# logic.net
KiCad netlist of a schematic drawn in EAGLE
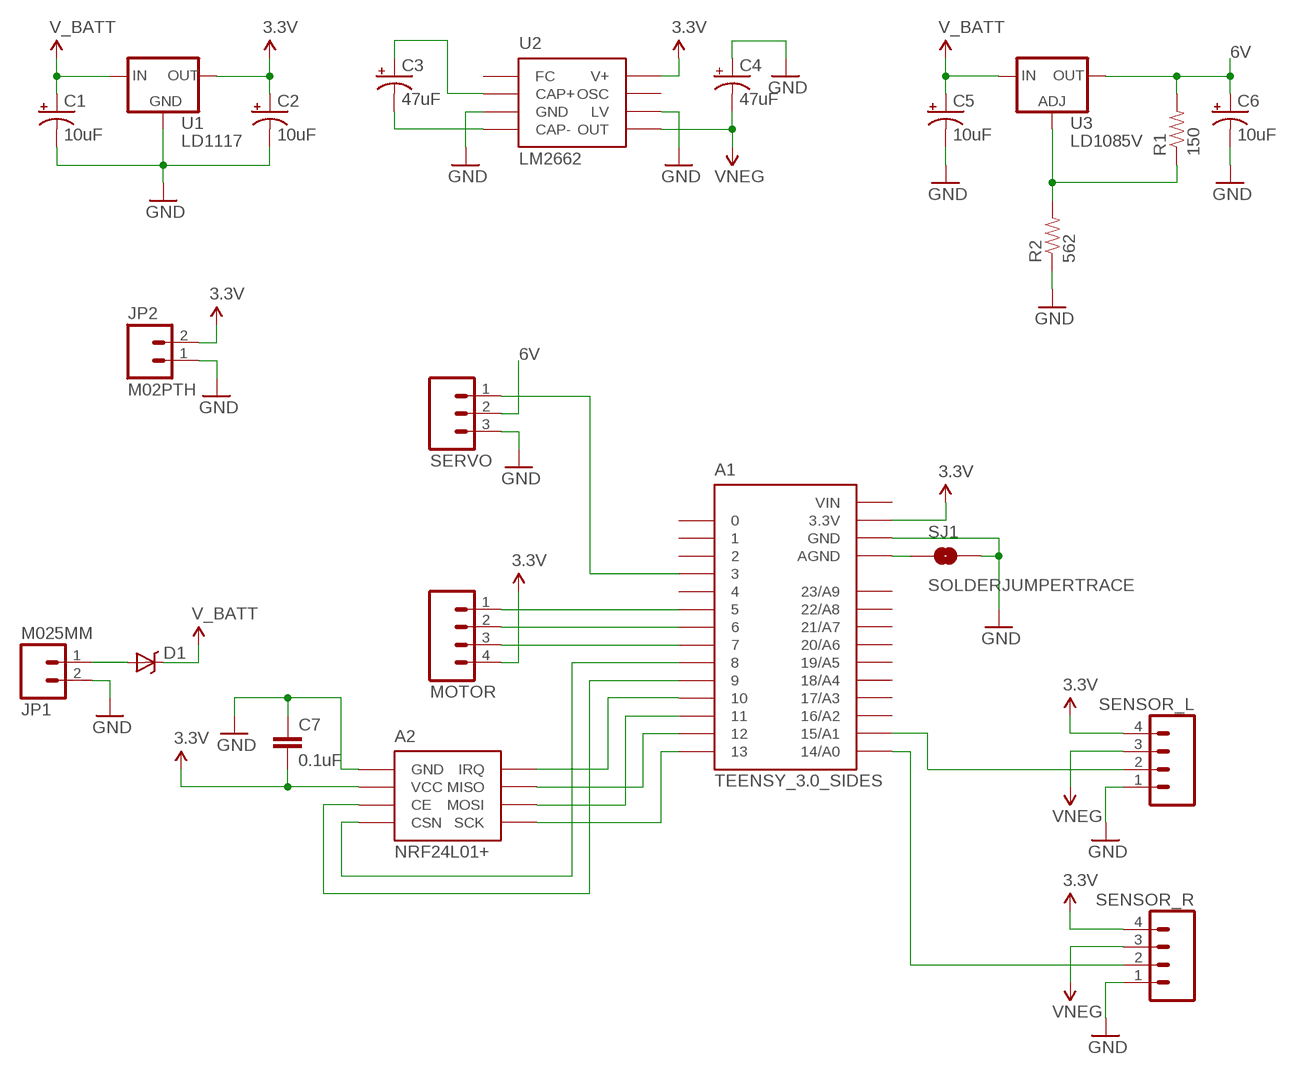
[diagram p0: schematic, sheet 1]

(export (version "E")
  (design (tool "Eeschema 10.0.6"))
  (components
    (comp (ref "A1")
      (value "TEENSY_3.0_SIDES")
      (footprint "eagle-import:TEENSY_3.0_SIDES")
      (libsource (lib "eagle-import") (part "TEENSY_3.0_SIDES"))
    )
    (comp (ref "A2")
      (value "NRF24L01+")
      (footprint "eagle-import:NRF24L01+")
      (libsource (lib "eagle-import") (part "NRF24L01+"))
    )
    (comp (ref "C1")
      (value "10uF")
      (footprint "eagle-import:E2-4")
      (libsource (lib "eagle-import") (part "CPOL-USE2-4"))
    )
    (comp (ref "C2")
      (value "10uF")
      (footprint "eagle-import:E2-4")
      (libsource (lib "eagle-import") (part "CPOL-USE2-4"))
    )
    (comp (ref "C3")
      (value "47uF")
      (footprint "eagle-import:CPOL-RADIAL-100UF-25V")
      (libsource (lib "eagle-import") (part "CAP_POLPTH1"))
    )
    (comp (ref "C4")
      (value "47uF")
      (footprint "eagle-import:CPOL-RADIAL-100UF-25V")
      (libsource (lib "eagle-import") (part "CAP_POLPTH1"))
    )
    (comp (ref "C5")
      (value "10uF")
      (footprint "eagle-import:E2-4")
      (libsource (lib "eagle-import") (part "CPOL-USE2-4"))
    )
    (comp (ref "C6")
      (value "10uF")
      (footprint "eagle-import:E2-4")
      (libsource (lib "eagle-import") (part "CPOL-USE2-4"))
    )
    (comp (ref "C7")
      (value "0.1uF")
      (footprint "eagle-import:0805")
      (libsource (lib "eagle-import") (part "CAP0805"))
    )
    (comp (ref "D1")
      (value "DIODE-SCHOTTKY_")
      (footprint "eagle-import:SMA-DIODE")
      (libsource (lib "eagle-import") (part "DIODE-SCHOTTKY_"))
    )
    (comp (ref "JP1")
      (value "M025MM")
      (footprint "eagle-import:SCREWTERMINAL-5MM-2")
      (libsource (lib "eagle-import") (part "M025MM"))
    )
    (comp (ref "JP2")
      (value "M02PTH")
      (footprint "eagle-import:1X02")
      (libsource (lib "eagle-import") (part "M02PTH"))
    )
    (comp (ref "MOTOR")
      (value "M04POLAR_LOCK")
      (footprint "eagle-import:MOLEX-1X4_LOCK")
      (libsource (lib "eagle-import") (part "M04POLAR_LOCK"))
    )
    (comp (ref "R1")
      (value "150")
      (footprint "eagle-import:0805")
      (libsource (lib "eagle-import") (part "RESISTOR0805-RES"))
    )
    (comp (ref "R2")
      (value "562")
      (footprint "eagle-import:0805")
      (libsource (lib "eagle-import") (part "RESISTOR0805-RES"))
    )
    (comp (ref "SENSOR_L")
      (value "M04POLAR_LOCK")
      (footprint "eagle-import:MOLEX-1X4_LOCK")
      (libsource (lib "eagle-import") (part "M04POLAR_LOCK"))
    )
    (comp (ref "SENSOR_R")
      (value "M04POLAR_LOCK")
      (footprint "eagle-import:MOLEX-1X4_LOCK")
      (libsource (lib "eagle-import") (part "M04POLAR_LOCK"))
    )
    (comp (ref "SERVO")
      (value "M03LOCK_LONGPADS")
      (footprint "eagle-import:1X03_LOCK_LONGPADS")
      (libsource (lib "eagle-import") (part "M03LOCK_LONGPADS"))
    )
    (comp (ref "SJ1")
      (value "SOLDERJUMPERTRACE")
      (footprint "eagle-import:SJ_2S-TRACE")
      (libsource (lib "eagle-import") (part "SOLDERJUMPERTRACE"))
    )
    (comp (ref "U1")
      (value "LD1117")
      (footprint "eagle-import:SOT-223")
      (libsource (lib "eagle-import") (part "LD1117"))
    )
    (comp (ref "U2")
      (value "LM2662")
      (footprint "eagle-import:SOIC-8")
      (libsource (lib "eagle-import") (part "LM2662"))
    )
    (comp (ref "U3")
      (value "LD1085V")
      (footprint "eagle-import:317TS")
      (libsource (lib "eagle-import") (part "LM317TS"))
    )
  )
  (nets
    (net (code "1") (name "/6V") (class "Default")
      (node (ref "C6") (pin "+") (pinfunction "+_+") (pintype "passive"))
      (node (ref "R1") (pin "2") (pinfunction "2_2") (pintype "passive"))
      (node (ref "SERVO") (pin "2") (pinfunction "2_2") (pintype "passive"))
      (node (ref "U3") (pin "2") (pinfunction "OUT_2") (pintype "passive"))
    )
    (net (code "2") (name "/VIN") (class "Default")
      (node (ref "A1") (pin "VIN") (pinfunction "VIN_VIN") (pintype "power_in"))
    )
    (net (code "3") (name "3.3V") (class "Default")
      (node (ref "A1") (pin "3.3V") (pinfunction "3.3V_3.3V") (pintype "power_in"))
      (node (ref "A2") (pin "2") (pinfunction "VCC_2") (pintype "bidirectional"))
      (node (ref "C2") (pin "+") (pinfunction "+_+") (pintype "passive"))
      (node (ref "C7") (pin "2") (pinfunction "2_2") (pintype "passive"))
      (node (ref "JP2") (pin "2") (pinfunction "2_2") (pintype "passive"))
      (node (ref "MOTOR") (pin "4") (pinfunction "4_4") (pintype "passive"))
      (node (ref "SENSOR_L") (pin "4") (pinfunction "4_4") (pintype "passive"))
      (node (ref "SENSOR_R") (pin "4") (pinfunction "4_4") (pintype "passive"))
      (node (ref "U1") (pin "2") (pinfunction "OUT_2") (pintype "passive"))
      (node (ref "U1") (pin "4") (pinfunction "OUT_4") (pintype "passive"))
      (node (ref "U2") (pin "8") (pinfunction "V+_8") (pintype "bidirectional"))
    )
    (net (code "4") (name "GND") (class "Default")
      (node (ref "A1") (pin "GND") (pinfunction "GND_GND") (pintype "power_in"))
      (node (ref "A2") (pin "1") (pinfunction "GND_1") (pintype "bidirectional"))
      (node (ref "C1") (pin "-") (pinfunction "-_-") (pintype "passive"))
      (node (ref "C2") (pin "-") (pinfunction "-_-") (pintype "passive"))
      (node (ref "C4") (pin "1") (pinfunction "+_1") (pintype "passive"))
      (node (ref "C5") (pin "-") (pinfunction "-_-") (pintype "passive"))
      (node (ref "C6") (pin "-") (pinfunction "-_-") (pintype "passive"))
      (node (ref "C7") (pin "1") (pinfunction "1_1") (pintype "passive"))
      (node (ref "JP1") (pin "2") (pinfunction "2_2") (pintype "passive"))
      (node (ref "JP2") (pin "1") (pinfunction "1_1") (pintype "passive"))
      (node (ref "R2") (pin "1") (pinfunction "1_1") (pintype "passive"))
      (node (ref "SENSOR_L") (pin "1") (pinfunction "1_1") (pintype "passive"))
      (node (ref "SENSOR_R") (pin "1") (pinfunction "1_1") (pintype "passive"))
      (node (ref "SERVO") (pin "3") (pinfunction "3_3") (pintype "passive"))
      (node (ref "SJ1") (pin "2") (pinfunction "2_2") (pintype "passive"))
      (node (ref "U1") (pin "1") (pinfunction "GND_1") (pintype "input"))
      (node (ref "U2") (pin "3") (pinfunction "GND_3") (pintype "bidirectional"))
      (node (ref "U2") (pin "6") (pinfunction "LV_6") (pintype "bidirectional"))
    )
    (net (code "5") (name "Net-(A1-Pad3)") (class "Default")
      (node (ref "A1") (pin "3") (pinfunction "3_3") (pintype "bidirectional"))
      (node (ref "SERVO") (pin "1") (pinfunction "1_1") (pintype "passive"))
    )
    (net (code "6") (name "Net-(A1-Pad5)") (class "Default")
      (node (ref "A1") (pin "5") (pinfunction "5_5") (pintype "bidirectional"))
      (node (ref "MOTOR") (pin "1") (pinfunction "1_1") (pintype "passive"))
    )
    (net (code "7") (name "Net-(A1-Pad6)") (class "Default")
      (node (ref "A1") (pin "6") (pinfunction "6_6") (pintype "bidirectional"))
      (node (ref "MOTOR") (pin "2") (pinfunction "2_2") (pintype "passive"))
    )
    (net (code "8") (name "Net-(A1-Pad7)") (class "Default")
      (node (ref "A1") (pin "7") (pinfunction "7_7") (pintype "bidirectional"))
      (node (ref "MOTOR") (pin "3") (pinfunction "3_3") (pintype "passive"))
    )
    (net (code "9") (name "Net-(A1-Pad14{slash}A0)") (class "Default")
      (node (ref "A1") (pin "14/A0") (pinfunction "14/A0_14/A0") (pintype "bidirectional"))
      (node (ref "SENSOR_R") (pin "2") (pinfunction "2_2") (pintype "passive"))
    )
    (net (code "10") (name "Net-(A1-Pad15{slash}A1)") (class "Default")
      (node (ref "A1") (pin "15/A1") (pinfunction "15/A1_15/A1") (pintype "bidirectional"))
      (node (ref "SENSOR_L") (pin "2") (pinfunction "2_2") (pintype "passive"))
    )
    (net (code "11") (name "Net-(A1-PadAGND)") (class "Default")
      (node (ref "A1") (pin "AGND") (pinfunction "AGND_AGND") (pintype "power_in"))
      (node (ref "SJ1") (pin "1") (pinfunction "1_1") (pintype "passive"))
    )
    (net (code "12") (name "Net-(A2-CE)") (class "Default")
      (node (ref "A1") (pin "9") (pinfunction "9_9") (pintype "bidirectional"))
      (node (ref "A2") (pin "3") (pinfunction "CE_3") (pintype "bidirectional"))
    )
    (net (code "13") (name "Net-(A2-CSN)") (class "Default")
      (node (ref "A1") (pin "8") (pinfunction "8_8") (pintype "bidirectional"))
      (node (ref "A2") (pin "4") (pinfunction "CSN_4") (pintype "bidirectional"))
    )
    (net (code "14") (name "Net-(A2-IRQ)") (class "Default")
      (node (ref "A1") (pin "10") (pinfunction "10_10") (pintype "bidirectional"))
      (node (ref "A2") (pin "8") (pinfunction "IRQ_8") (pintype "bidirectional"))
    )
    (net (code "15") (name "Net-(A2-MISO)") (class "Default")
      (node (ref "A1") (pin "12") (pinfunction "12_12") (pintype "bidirectional"))
      (node (ref "A2") (pin "7") (pinfunction "MISO_7") (pintype "bidirectional"))
    )
    (net (code "16") (name "Net-(A2-MOSI)") (class "Default")
      (node (ref "A1") (pin "11") (pinfunction "11_11") (pintype "bidirectional"))
      (node (ref "A2") (pin "6") (pinfunction "MOSI_6") (pintype "bidirectional"))
    )
    (net (code "17") (name "Net-(A2-SCK)") (class "Default")
      (node (ref "A1") (pin "13") (pinfunction "13_13") (pintype "bidirectional"))
      (node (ref "A2") (pin "5") (pinfunction "SCK_5") (pintype "bidirectional"))
    )
    (net (code "18") (name "Net-(C3-+)") (class "Default")
      (node (ref "C3") (pin "1") (pinfunction "+_1") (pintype "passive"))
      (node (ref "U2") (pin "2") (pinfunction "CAP+_2") (pintype "bidirectional"))
    )
    (net (code "19") (name "Net-(C3--)") (class "Default")
      (node (ref "C3") (pin "2") (pinfunction "-_2") (pintype "passive"))
      (node (ref "U2") (pin "4") (pinfunction "CAP-_4") (pintype "bidirectional"))
    )
    (net (code "20") (name "Net-(D1-PadA)") (class "Default")
      (node (ref "D1") (pin "A") (pinfunction "A_A") (pintype "passive"))
      (node (ref "JP1") (pin "1") (pinfunction "1_1") (pintype "passive"))
    )
    (net (code "21") (name "Net-(U3-ADJ)") (class "Default")
      (node (ref "R1") (pin "1") (pinfunction "1_1") (pintype "passive"))
      (node (ref "R2") (pin "2") (pinfunction "2_2") (pintype "passive"))
      (node (ref "U3") (pin "1") (pinfunction "ADJ_1") (pintype "input"))
    )
    (net (code "22") (name "VNEG") (class "Default")
      (node (ref "C4") (pin "2") (pinfunction "-_2") (pintype "passive"))
      (node (ref "SENSOR_L") (pin "3") (pinfunction "3_3") (pintype "passive"))
      (node (ref "SENSOR_R") (pin "3") (pinfunction "3_3") (pintype "passive"))
      (node (ref "U2") (pin "5") (pinfunction "OUT_5") (pintype "bidirectional"))
    )
    (net (code "23") (name "V_BATT") (class "Default")
      (node (ref "C1") (pin "+") (pinfunction "+_+") (pintype "passive"))
      (node (ref "C5") (pin "+") (pinfunction "+_+") (pintype "passive"))
      (node (ref "D1") (pin "C") (pinfunction "C_C") (pintype "passive"))
      (node (ref "U1") (pin "3") (pinfunction "IN_3") (pintype "input"))
      (node (ref "U3") (pin "3") (pinfunction "IN_3") (pintype "input"))
    )
    (net (code "24") (name "unconnected-(A1-Pad0)") (class "Default")
      (node (ref "A1") (pin "0") (pinfunction "0_0") (pintype "bidirectional"))
    )
    (net (code "25") (name "unconnected-(A1-Pad1)") (class "Default")
      (node (ref "A1") (pin "1") (pinfunction "1_1") (pintype "bidirectional"))
    )
    (net (code "26") (name "unconnected-(A1-Pad2)") (class "Default")
      (node (ref "A1") (pin "2") (pinfunction "2_2") (pintype "bidirectional"))
    )
    (net (code "27") (name "unconnected-(A1-Pad4)") (class "Default")
      (node (ref "A1") (pin "4") (pinfunction "4_4") (pintype "bidirectional"))
    )
    (net (code "28") (name "unconnected-(A1-Pad16{slash}A2)") (class "Default")
      (node (ref "A1") (pin "16/A2") (pinfunction "16/A2_16/A2") (pintype "bidirectional"))
    )
    (net (code "29") (name "unconnected-(A1-Pad17{slash}A3)") (class "Default")
      (node (ref "A1") (pin "17/A3") (pinfunction "17/A3_17/A3") (pintype "bidirectional"))
    )
    (net (code "30") (name "unconnected-(A1-Pad18{slash}A4)") (class "Default")
      (node (ref "A1") (pin "18/A4") (pinfunction "18/A4_18/A4") (pintype "bidirectional"))
    )
    (net (code "31") (name "unconnected-(A1-Pad19{slash}A5)") (class "Default")
      (node (ref "A1") (pin "19/A5") (pinfunction "19/A5_19/A5") (pintype "bidirectional"))
    )
    (net (code "32") (name "unconnected-(A1-Pad20{slash}A6)") (class "Default")
      (node (ref "A1") (pin "20/A6") (pinfunction "20/A6_20/A6") (pintype "bidirectional"))
    )
    (net (code "33") (name "unconnected-(A1-Pad21{slash}A7)") (class "Default")
      (node (ref "A1") (pin "21/A7") (pinfunction "21/A7_21/A7") (pintype "bidirectional"))
    )
    (net (code "34") (name "unconnected-(A1-Pad22{slash}A8)") (class "Default")
      (node (ref "A1") (pin "22/A8") (pinfunction "22/A8_22/A8") (pintype "bidirectional"))
    )
    (net (code "35") (name "unconnected-(A1-Pad23{slash}A9)") (class "Default")
      (node (ref "A1") (pin "23/A9") (pinfunction "23/A9_23/A9") (pintype "bidirectional"))
    )
    (net (code "36") (name "unconnected-(U2-FC-Pad1)") (class "Default")
      (node (ref "U2") (pin "1") (pinfunction "FC_1") (pintype "bidirectional"))
    )
    (net (code "37") (name "unconnected-(U2-OSC-Pad7)") (class "Default")
      (node (ref "U2") (pin "7") (pinfunction "OSC_7") (pintype "bidirectional"))
    )
  )
)
